# MO02.net
KiCad netlist of a schematic drawn in EAGLE
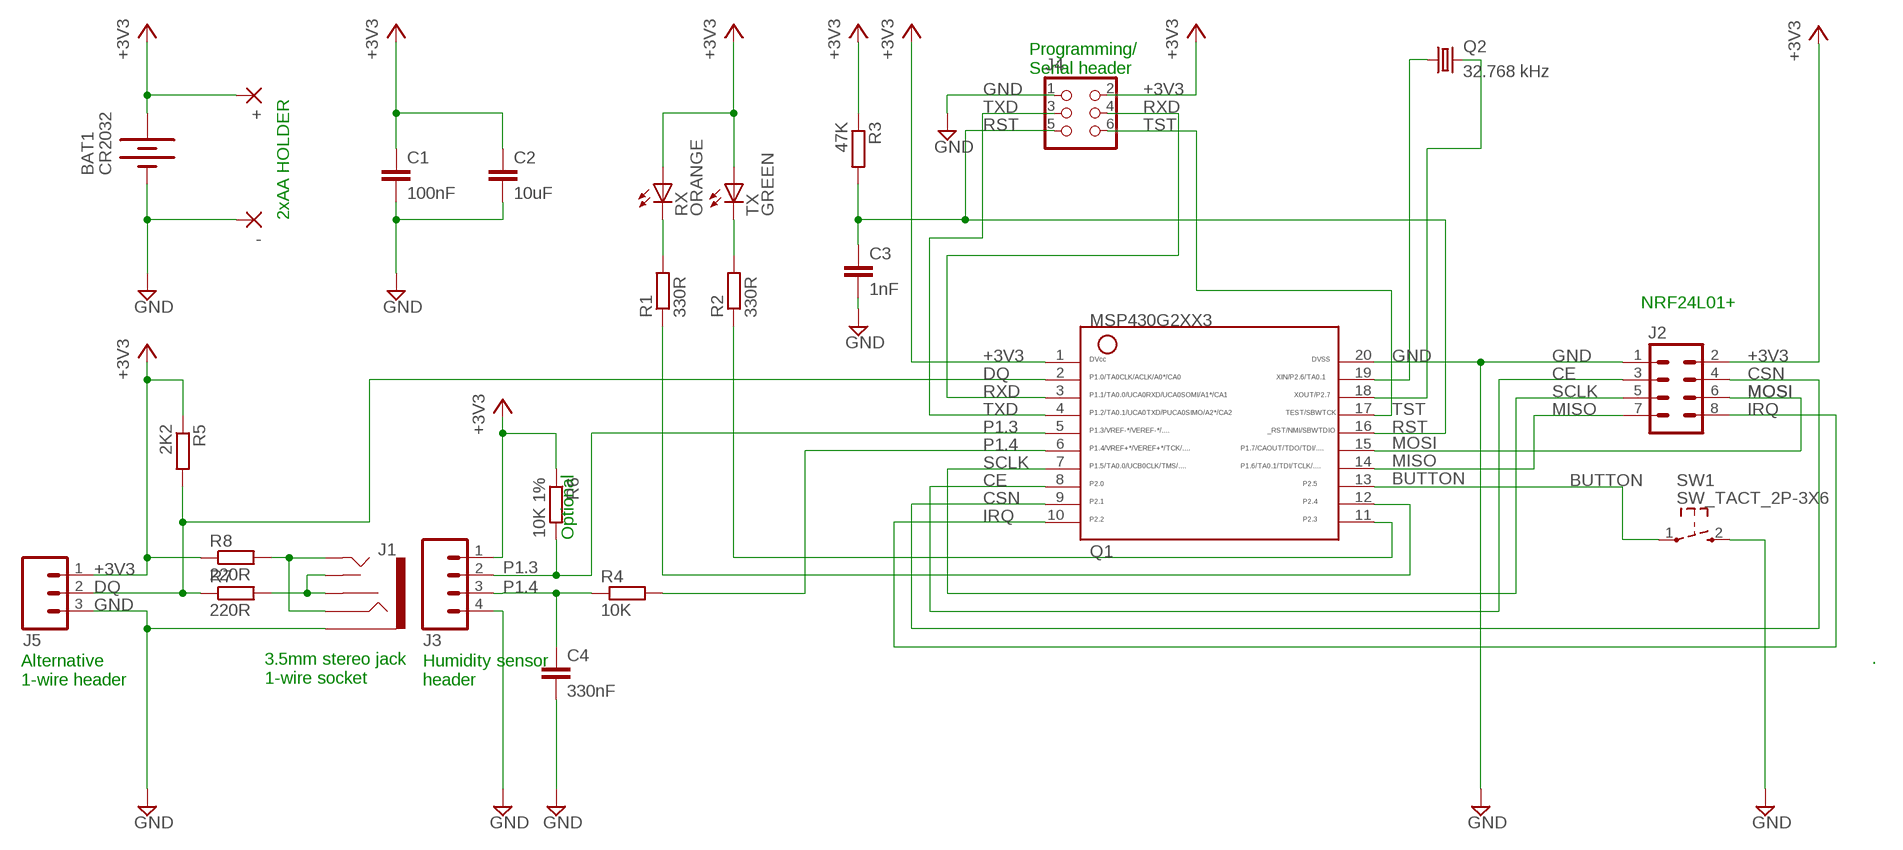
[diagram p0: schematic, sheet 1]

(export (version "E")
  (design (tool "Eeschema 10.0.6"))
  (components
    (comp (ref "+")
      (value "2,54/1,0")
      (footprint "eagle-import:2,54_1,0")
      (libsource (lib "eagle-import") (part "2,54/1,0"))
    )
    (comp (ref "-")
      (value "2,54/1,0")
      (footprint "eagle-import:2,54_1,0")
      (libsource (lib "eagle-import") (part "2,54/1,0"))
    )
    (comp (ref "BAT1")
      (value "CR2032")
      (footprint "eagle-import:BATTCOM_20MM_PTH")
      (libsource (lib "eagle-import") (part "BATTERY20PTH"))
    )
    (comp (ref "C1")
      (value "100nF")
      (footprint "eagle-import:C0805")
      (libsource (lib "eagle-import") (part "resistor_C-EUC0805"))
    )
    (comp (ref "C2")
      (value "10uF")
      (footprint "eagle-import:C1206")
      (libsource (lib "eagle-import") (part "C-EUC1206"))
    )
    (comp (ref "C3")
      (value "1nF")
      (footprint "eagle-import:C0805")
      (libsource (lib "eagle-import") (part "resistor_C-EUC0805"))
    )
    (comp (ref "C4")
      (value "330nF")
      (footprint "eagle-import:C0805")
      (libsource (lib "eagle-import") (part "resistor_C-EUC0805"))
    )
    (comp (ref "J1")
      (value "AUDIO-JACK2PTH")
      (footprint "eagle-import:AUDIO-JACK")
      (libsource (lib "eagle-import") (part "AUDIO-JACK2PTH"))
    )
    (comp (ref "J2")
      (value "M04X2")
      (footprint "eagle-import:2X4")
      (libsource (lib "eagle-import") (part "M04X2"))
    )
    (comp (ref "J3")
      (value "M04PTH")
      (footprint "eagle-import:1X04")
      (libsource (lib "eagle-import") (part "M04PTH"))
    )
    (comp (ref "J4")
      (value "CON_HEADER_2X03-PTH")
      (footprint "eagle-import:M2X3")
      (libsource (lib "eagle-import") (part "CON_HEADER_2X03-PTH"))
    )
    (comp (ref "J5")
      (value "M03PTH")
      (footprint "eagle-import:1X03")
      (libsource (lib "eagle-import") (part "M03PTH"))
    )
    (comp (ref "Q1")
      (value "G2XX3---PW20")
      (footprint "eagle-import:PW20")
      (libsource (lib "eagle-import") (part "G2XX3---PW20"))
    )
    (comp (ref "Q2")
      (value "32.768 kHz")
      (footprint "eagle-import:TC26H")
      (libsource (lib "eagle-import") (part "CRYSTALTC26H"))
    )
    (comp (ref "R1")
      (value "330R")
      (footprint "eagle-import:M0805")
      (fields (field (name "RESISTANCE") "4K7"))
      (libsource (lib "eagle-import") (part "R-EU_M0805"))
    )
    (comp (ref "R2")
      (value "330R")
      (footprint "eagle-import:M0805")
      (fields (field (name "RESISTANCE") "4K7"))
      (libsource (lib "eagle-import") (part "R-EU_M0805"))
    )
    (comp (ref "R3")
      (value "47K")
      (footprint "eagle-import:M0805")
      (fields (field (name "RESISTANCE") "4K7"))
      (libsource (lib "eagle-import") (part "R-EU_M0805"))
    )
    (comp (ref "R4")
      (value "10K")
      (footprint "eagle-import:M0805")
      (fields (field (name "RESISTANCE") "4K7"))
      (libsource (lib "eagle-import") (part "R-EU_M0805"))
    )
    (comp (ref "R5")
      (value "2K2")
      (footprint "eagle-import:M0805")
      (fields (field (name "RESISTANCE") "4K7"))
      (libsource (lib "eagle-import") (part "R-EU_M0805"))
    )
    (comp (ref "R6")
      (value "10K 1%")
      (footprint "eagle-import:M0805")
      (fields (field (name "RESISTANCE") "4K7"))
      (libsource (lib "eagle-import") (part "R-EU_M0805"))
    )
    (comp (ref "R7")
      (value "220R")
      (footprint "eagle-import:M0805")
      (fields (field (name "RESISTANCE") "4K7"))
      (libsource (lib "eagle-import") (part "R-EU_M0805"))
    )
    (comp (ref "R8")
      (value "220R")
      (footprint "eagle-import:M0805")
      (fields (field (name "RESISTANCE") "4K7"))
      (libsource (lib "eagle-import") (part "R-EU_M0805"))
    )
    (comp (ref "RX")
      (value "ORANGE")
      (footprint "eagle-import:CHIPLED_0805")
      (libsource (lib "eagle-import") (part "LEDCHIPLED_0805"))
    )
    (comp (ref "SW1")
      (value "SW_TACT_2P-3X6")
      (footprint "eagle-import:SW_TACT_3X6")
      (libsource (lib "eagle-import") (part "SW_TACT_2P-3X6"))
    )
    (comp (ref "TX")
      (value "GREEN")
      (footprint "eagle-import:CHIPLED_0805")
      (libsource (lib "eagle-import") (part "LEDCHIPLED_0805"))
    )
  )
  (nets
    (net (code "1") (name "+3V3") (class "Default")
      (node (ref "+") (pin "1") (pinfunction "P_1") (pintype "passive"))
      (node (ref "BAT1") (pin "1") (pinfunction "+_1") (pintype "power_in"))
      (node (ref "C1") (pin "1") (pinfunction "1_1") (pintype "passive"))
      (node (ref "C2") (pin "1") (pinfunction "1_1") (pintype "passive"))
      (node (ref "J2") (pin "2") (pinfunction "2_2") (pintype "passive"))
      (node (ref "J3") (pin "1") (pinfunction "1_1") (pintype "passive"))
      (node (ref "J4") (pin "2") (pinfunction "2_2") (pintype "passive"))
      (node (ref "J5") (pin "1") (pinfunction "1_1") (pintype "passive"))
      (node (ref "Q1") (pin "1") (pinfunction "1_1") (pintype "bidirectional"))
      (node (ref "R3") (pin "1") (pinfunction "1_1") (pintype "passive"))
      (node (ref "R5") (pin "1") (pinfunction "1_1") (pintype "passive"))
      (node (ref "R6") (pin "1") (pinfunction "1_1") (pintype "passive"))
      (node (ref "R8") (pin "1") (pinfunction "1_1") (pintype "passive"))
      (node (ref "RX") (pin "A") (pinfunction "A_A") (pintype "passive"))
      (node (ref "TX") (pin "A") (pinfunction "A_A") (pintype "passive"))
    )
    (net (code "2") (name "/BUTTON") (class "Default")
      (node (ref "Q1") (pin "13") (pinfunction "13_13") (pintype "bidirectional"))
      (node (ref "SW1") (pin "1") (pinfunction "1_1") (pintype "passive"))
    )
    (net (code "3") (name "/CE") (class "Default")
      (node (ref "J2") (pin "3") (pinfunction "3_3") (pintype "passive"))
      (node (ref "Q1") (pin "8") (pinfunction "8_8") (pintype "bidirectional"))
    )
    (net (code "4") (name "/CSN") (class "Default")
      (node (ref "J2") (pin "4") (pinfunction "4_4") (pintype "passive"))
      (node (ref "Q1") (pin "9") (pinfunction "9_9") (pintype "bidirectional"))
    )
    (net (code "5") (name "/DQ") (class "Default")
      (node (ref "J5") (pin "2") (pinfunction "2_2") (pintype "passive"))
      (node (ref "Q1") (pin "2") (pinfunction "2_2") (pintype "bidirectional"))
      (node (ref "R5") (pin "2") (pinfunction "2_2") (pintype "passive"))
      (node (ref "R7") (pin "1") (pinfunction "1_1") (pintype "passive"))
    )
    (net (code "6") (name "/IRQ") (class "Default")
      (node (ref "J2") (pin "8") (pinfunction "8_8") (pintype "passive"))
      (node (ref "Q1") (pin "10") (pinfunction "10_10") (pintype "bidirectional"))
    )
    (net (code "7") (name "/MISO") (class "Default")
      (node (ref "J2") (pin "7") (pinfunction "7_7") (pintype "passive"))
      (node (ref "Q1") (pin "14") (pinfunction "14_14") (pintype "bidirectional"))
    )
    (net (code "8") (name "/MOSI") (class "Default")
      (node (ref "J2") (pin "6") (pinfunction "6_6") (pintype "passive"))
      (node (ref "Q1") (pin "15") (pinfunction "15_15") (pintype "bidirectional"))
    )
    (net (code "9") (name "/P1.3") (class "Default")
      (node (ref "J3") (pin "2") (pinfunction "2_2") (pintype "passive"))
      (node (ref "Q1") (pin "5") (pinfunction "5_5") (pintype "bidirectional"))
      (node (ref "R6") (pin "2") (pinfunction "2_2") (pintype "passive"))
    )
    (net (code "10") (name "/P1.4") (class "Default")
      (node (ref "Q1") (pin "6") (pinfunction "6_6") (pintype "bidirectional"))
      (node (ref "R4") (pin "2") (pinfunction "2_2") (pintype "passive"))
    )
    (net (code "11") (name "/RST") (class "Default")
      (node (ref "C3") (pin "1") (pinfunction "1_1") (pintype "passive"))
      (node (ref "J4") (pin "5") (pinfunction "5_5") (pintype "passive"))
      (node (ref "Q1") (pin "16") (pinfunction "16_16") (pintype "bidirectional"))
      (node (ref "R3") (pin "2") (pinfunction "2_2") (pintype "passive"))
    )
    (net (code "12") (name "/RXD") (class "Default")
      (node (ref "J4") (pin "4") (pinfunction "4_4") (pintype "passive"))
      (node (ref "Q1") (pin "3") (pinfunction "3_3") (pintype "bidirectional"))
    )
    (net (code "13") (name "/SCLK") (class "Default")
      (node (ref "J2") (pin "5") (pinfunction "5_5") (pintype "passive"))
      (node (ref "Q1") (pin "7") (pinfunction "7_7") (pintype "bidirectional"))
    )
    (net (code "14") (name "/TST") (class "Default")
      (node (ref "J4") (pin "6") (pinfunction "6_6") (pintype "passive"))
      (node (ref "Q1") (pin "17") (pinfunction "17_17") (pintype "bidirectional"))
    )
    (net (code "15") (name "/TXD") (class "Default")
      (node (ref "J4") (pin "3") (pinfunction "3_3") (pintype "passive"))
      (node (ref "Q1") (pin "4") (pinfunction "4_4") (pintype "bidirectional"))
    )
    (net (code "16") (name "GND") (class "Default")
      (node (ref "-") (pin "1") (pinfunction "P_1") (pintype "passive"))
      (node (ref "BAT1") (pin "2") (pinfunction "-_2") (pintype "power_in"))
      (node (ref "C1") (pin "2") (pinfunction "2_2") (pintype "passive"))
      (node (ref "C2") (pin "2") (pinfunction "2_2") (pintype "passive"))
      (node (ref "C3") (pin "2") (pinfunction "2_2") (pintype "passive"))
      (node (ref "C4") (pin "2") (pinfunction "2_2") (pintype "passive"))
      (node (ref "J1") (pin "SLEEVE") (pinfunction "SLEEVE_SLEEVE") (pintype "bidirectional"))
      (node (ref "J2") (pin "1") (pinfunction "1_1") (pintype "passive"))
      (node (ref "J3") (pin "4") (pinfunction "4_4") (pintype "passive"))
      (node (ref "J4") (pin "1") (pinfunction "1_1") (pintype "passive"))
      (node (ref "J5") (pin "3") (pinfunction "3_3") (pintype "passive"))
      (node (ref "Q1") (pin "20") (pinfunction "20_20") (pintype "bidirectional"))
      (node (ref "SW1") (pin "2") (pinfunction "3_2") (pintype "passive"))
    )
    (net (code "17") (name "Net-(C4-Pad1)") (class "Default")
      (node (ref "C4") (pin "1") (pinfunction "1_1") (pintype "passive"))
      (node (ref "J3") (pin "3") (pinfunction "3_3") (pintype "passive"))
      (node (ref "R4") (pin "1") (pinfunction "1_1") (pintype "passive"))
    )
    (net (code "18") (name "Net-(J1-PadRING)") (class "Default")
      (node (ref "J1") (pin "RING") (pinfunction "RING_RING") (pintype "bidirectional"))
      (node (ref "J1") (pin "TIP") (pinfunction "TIP_TIP") (pintype "bidirectional"))
      (node (ref "R8") (pin "2") (pinfunction "2_2") (pintype "passive"))
    )
    (net (code "19") (name "Net-(J1-PadRSH)") (class "Default")
      (node (ref "J1") (pin "RSH") (pinfunction "RSH_RSH") (pintype "bidirectional"))
      (node (ref "J1") (pin "TSH") (pinfunction "TSH_TSH") (pintype "bidirectional"))
      (node (ref "R7") (pin "2") (pinfunction "2_2") (pintype "passive"))
    )
    (net (code "20") (name "Net-(Q1-Pad11)") (class "Default")
      (node (ref "Q1") (pin "11") (pinfunction "11_11") (pintype "bidirectional"))
      (node (ref "R2") (pin "1") (pinfunction "1_1") (pintype "passive"))
    )
    (net (code "21") (name "Net-(Q1-Pad12)") (class "Default")
      (node (ref "Q1") (pin "12") (pinfunction "12_12") (pintype "bidirectional"))
      (node (ref "R1") (pin "1") (pinfunction "1_1") (pintype "passive"))
    )
    (net (code "22") (name "Net-(Q1-Pad18)") (class "Default")
      (node (ref "Q1") (pin "18") (pinfunction "18_18") (pintype "bidirectional"))
      (node (ref "Q2") (pin "2") (pinfunction "2_2") (pintype "passive"))
    )
    (net (code "23") (name "Net-(Q1-Pad19)") (class "Default")
      (node (ref "Q1") (pin "19") (pinfunction "19_19") (pintype "bidirectional"))
      (node (ref "Q2") (pin "1") (pinfunction "1_1") (pintype "passive"))
    )
    (net (code "24") (name "Net-(R1-Pad2)") (class "Default")
      (node (ref "R1") (pin "2") (pinfunction "2_2") (pintype "passive"))
      (node (ref "RX") (pin "C") (pinfunction "C_C") (pintype "passive"))
    )
    (net (code "25") (name "Net-(R2-Pad2)") (class "Default")
      (node (ref "R2") (pin "2") (pinfunction "2_2") (pintype "passive"))
      (node (ref "TX") (pin "C") (pinfunction "C_C") (pintype "passive"))
    )
  )
)
